# BI16.net
KiCad netlist of a schematic drawn in EAGLE
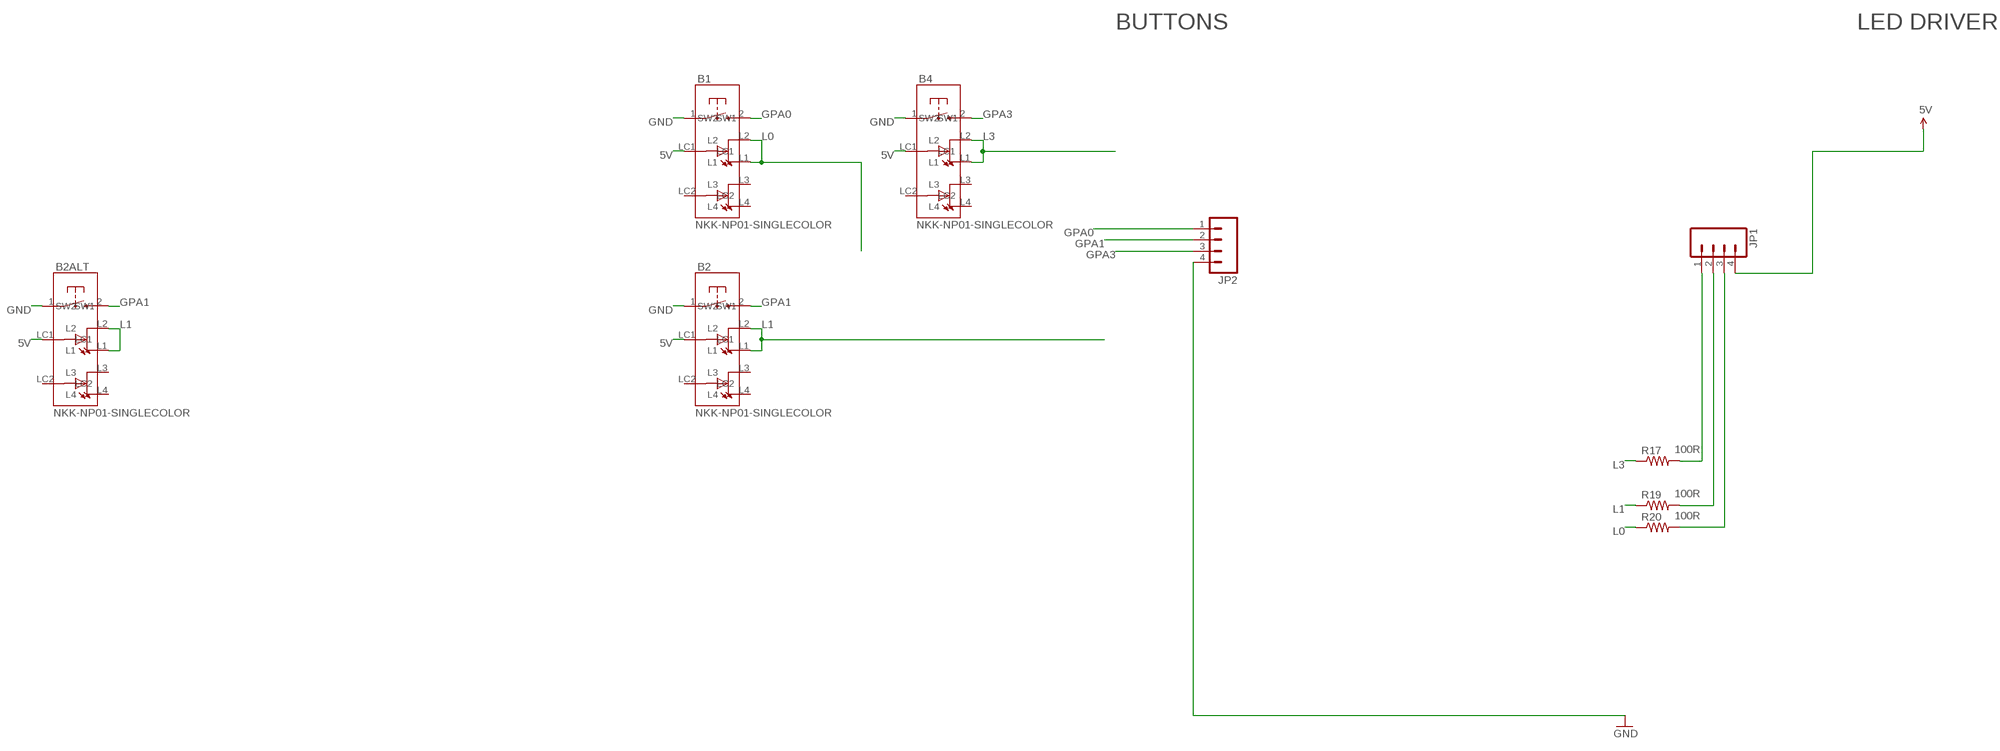
[diagram p0: schematic, sheet 1]

(export (version "E")
  (design (tool "Eeschema 10.0.6"))
  (components
    (comp (ref "B1")
      (value "NKK-NP01-SINGLECOLOR")
      (footprint "eagle-import:NKK-NP01")
      (libsource (lib "eagle-import") (part "NKK-NP01-SINGLECOLOR"))
    )
    (comp (ref "B2")
      (value "NKK-NP01-SINGLECOLOR")
      (footprint "eagle-import:NKK-NP01")
      (libsource (lib "eagle-import") (part "NKK-NP01-SINGLECOLOR"))
    )
    (comp (ref "B2ALT")
      (value "NKK-NP01-SINGLECOLOR")
      (footprint "eagle-import:NKK-NP01")
      (libsource (lib "eagle-import") (part "NKK-NP01-SINGLECOLOR"))
    )
    (comp (ref "B4")
      (value "NKK-NP01-SINGLECOLOR")
      (footprint "eagle-import:NKK-NP01")
      (libsource (lib "eagle-import") (part "NKK-NP01-SINGLECOLOR"))
    )
    (comp (ref "JP1")
      (value "M04LOCK")
      (footprint "eagle-import:1X04_LOCK")
      (libsource (lib "eagle-import") (part "M04LOCK"))
    )
    (comp (ref "JP2")
      (value "M04LOCK")
      (footprint "eagle-import:1X04_LOCK")
      (libsource (lib "eagle-import") (part "M04LOCK"))
    )
    (comp (ref "R17")
      (value "100R")
      (footprint "eagle-import:0603-RES")
      (libsource (lib "eagle-import") (part "RESISTOR0603-RES"))
    )
    (comp (ref "R19")
      (value "100R")
      (footprint "eagle-import:0603-RES")
      (libsource (lib "eagle-import") (part "RESISTOR0603-RES"))
    )
    (comp (ref "R20")
      (value "100R")
      (footprint "eagle-import:0603-RES")
      (libsource (lib "eagle-import") (part "RESISTOR0603-RES"))
    )
  )
  (nets
    (net (code "1") (name "5V") (class "Default")
      (node (ref "B1") (pin "LC1") (pinfunction "LC1_LC1") (pintype "bidirectional"))
      (node (ref "B2") (pin "LC1") (pinfunction "LC1_LC1") (pintype "bidirectional"))
      (node (ref "B2ALT") (pin "LC1") (pinfunction "LC1_LC1") (pintype "bidirectional"))
      (node (ref "B4") (pin "LC1") (pinfunction "LC1_LC1") (pintype "bidirectional"))
      (node (ref "JP1") (pin "4") (pinfunction "4_4") (pintype "passive"))
    )
    (net (code "2") (name "GND") (class "Default")
      (node (ref "B1") (pin "1") (pinfunction "SW1_1") (pintype "bidirectional"))
      (node (ref "B2") (pin "1") (pinfunction "SW1_1") (pintype "bidirectional"))
      (node (ref "B2ALT") (pin "1") (pinfunction "SW1_1") (pintype "bidirectional"))
      (node (ref "B4") (pin "1") (pinfunction "SW1_1") (pintype "bidirectional"))
      (node (ref "JP2") (pin "4") (pinfunction "4_4") (pintype "passive"))
    )
    (net (code "3") (name "GPA0") (class "Default")
      (node (ref "B1") (pin "2") (pinfunction "SW2_2") (pintype "bidirectional"))
      (node (ref "JP2") (pin "1") (pinfunction "1_1") (pintype "passive"))
    )
    (net (code "4") (name "GPA1") (class "Default")
      (node (ref "B2") (pin "2") (pinfunction "SW2_2") (pintype "bidirectional"))
      (node (ref "B2ALT") (pin "2") (pinfunction "SW2_2") (pintype "bidirectional"))
      (node (ref "JP2") (pin "2") (pinfunction "2_2") (pintype "passive"))
    )
    (net (code "5") (name "GPA3") (class "Default")
      (node (ref "B4") (pin "2") (pinfunction "SW2_2") (pintype "bidirectional"))
      (node (ref "JP2") (pin "3") (pinfunction "3_3") (pintype "passive"))
    )
    (net (code "6") (name "L0") (class "Default")
      (node (ref "B1") (pin "L1") (pinfunction "L1_L1") (pintype "bidirectional"))
      (node (ref "B1") (pin "L2") (pinfunction "L2_L2") (pintype "bidirectional"))
      (node (ref "R20") (pin "1") (pinfunction "1_1") (pintype "passive"))
    )
    (net (code "7") (name "L1") (class "Default")
      (node (ref "B2") (pin "L1") (pinfunction "L1_L1") (pintype "bidirectional"))
      (node (ref "B2") (pin "L2") (pinfunction "L2_L2") (pintype "bidirectional"))
      (node (ref "B2ALT") (pin "L1") (pinfunction "L1_L1") (pintype "bidirectional"))
      (node (ref "B2ALT") (pin "L2") (pinfunction "L2_L2") (pintype "bidirectional"))
      (node (ref "R19") (pin "1") (pinfunction "1_1") (pintype "passive"))
    )
    (net (code "8") (name "L3") (class "Default")
      (node (ref "B4") (pin "L1") (pinfunction "L1_L1") (pintype "bidirectional"))
      (node (ref "B4") (pin "L2") (pinfunction "L2_L2") (pintype "bidirectional"))
      (node (ref "R17") (pin "1") (pinfunction "1_1") (pintype "passive"))
    )
    (net (code "9") (name "Net-(JP1-Pad1)") (class "Default")
      (node (ref "JP1") (pin "1") (pinfunction "1_1") (pintype "passive"))
      (node (ref "R17") (pin "2") (pinfunction "2_2") (pintype "passive"))
    )
    (net (code "10") (name "Net-(JP1-Pad2)") (class "Default")
      (node (ref "JP1") (pin "2") (pinfunction "2_2") (pintype "passive"))
      (node (ref "R19") (pin "2") (pinfunction "2_2") (pintype "passive"))
    )
    (net (code "11") (name "Net-(JP1-Pad3)") (class "Default")
      (node (ref "JP1") (pin "3") (pinfunction "3_3") (pintype "passive"))
      (node (ref "R20") (pin "2") (pinfunction "2_2") (pintype "passive"))
    )
    (net (code "12") (name "unconnected-(B1-PadL3)") (class "Default")
      (node (ref "B1") (pin "L3") (pinfunction "L3_L3") (pintype "bidirectional"))
    )
    (net (code "13") (name "unconnected-(B1-PadL4)") (class "Default")
      (node (ref "B1") (pin "L4") (pinfunction "L4_L4") (pintype "bidirectional"))
    )
    (net (code "14") (name "unconnected-(B1-PadLC2)") (class "Default")
      (node (ref "B1") (pin "LC2") (pinfunction "LC2_LC2") (pintype "bidirectional"))
    )
    (net (code "15") (name "unconnected-(B2-PadL3)") (class "Default")
      (node (ref "B2") (pin "L3") (pinfunction "L3_L3") (pintype "bidirectional"))
    )
    (net (code "16") (name "unconnected-(B2-PadL4)") (class "Default")
      (node (ref "B2") (pin "L4") (pinfunction "L4_L4") (pintype "bidirectional"))
    )
    (net (code "17") (name "unconnected-(B2-PadLC2)") (class "Default")
      (node (ref "B2") (pin "LC2") (pinfunction "LC2_LC2") (pintype "bidirectional"))
    )
    (net (code "18") (name "unconnected-(B2ALT-PadL3)") (class "Default")
      (node (ref "B2ALT") (pin "L3") (pinfunction "L3_L3") (pintype "bidirectional"))
    )
    (net (code "19") (name "unconnected-(B2ALT-PadL4)") (class "Default")
      (node (ref "B2ALT") (pin "L4") (pinfunction "L4_L4") (pintype "bidirectional"))
    )
    (net (code "20") (name "unconnected-(B2ALT-PadLC2)") (class "Default")
      (node (ref "B2ALT") (pin "LC2") (pinfunction "LC2_LC2") (pintype "bidirectional"))
    )
    (net (code "21") (name "unconnected-(B4-PadL3)") (class "Default")
      (node (ref "B4") (pin "L3") (pinfunction "L3_L3") (pintype "bidirectional"))
    )
    (net (code "22") (name "unconnected-(B4-PadL4)") (class "Default")
      (node (ref "B4") (pin "L4") (pinfunction "L4_L4") (pintype "bidirectional"))
    )
    (net (code "23") (name "unconnected-(B4-PadLC2)") (class "Default")
      (node (ref "B4") (pin "LC2") (pinfunction "LC2_LC2") (pintype "bidirectional"))
    )
  )
)
